# StairLights_screw.net
KiCad netlist of a schematic drawn in EAGLE
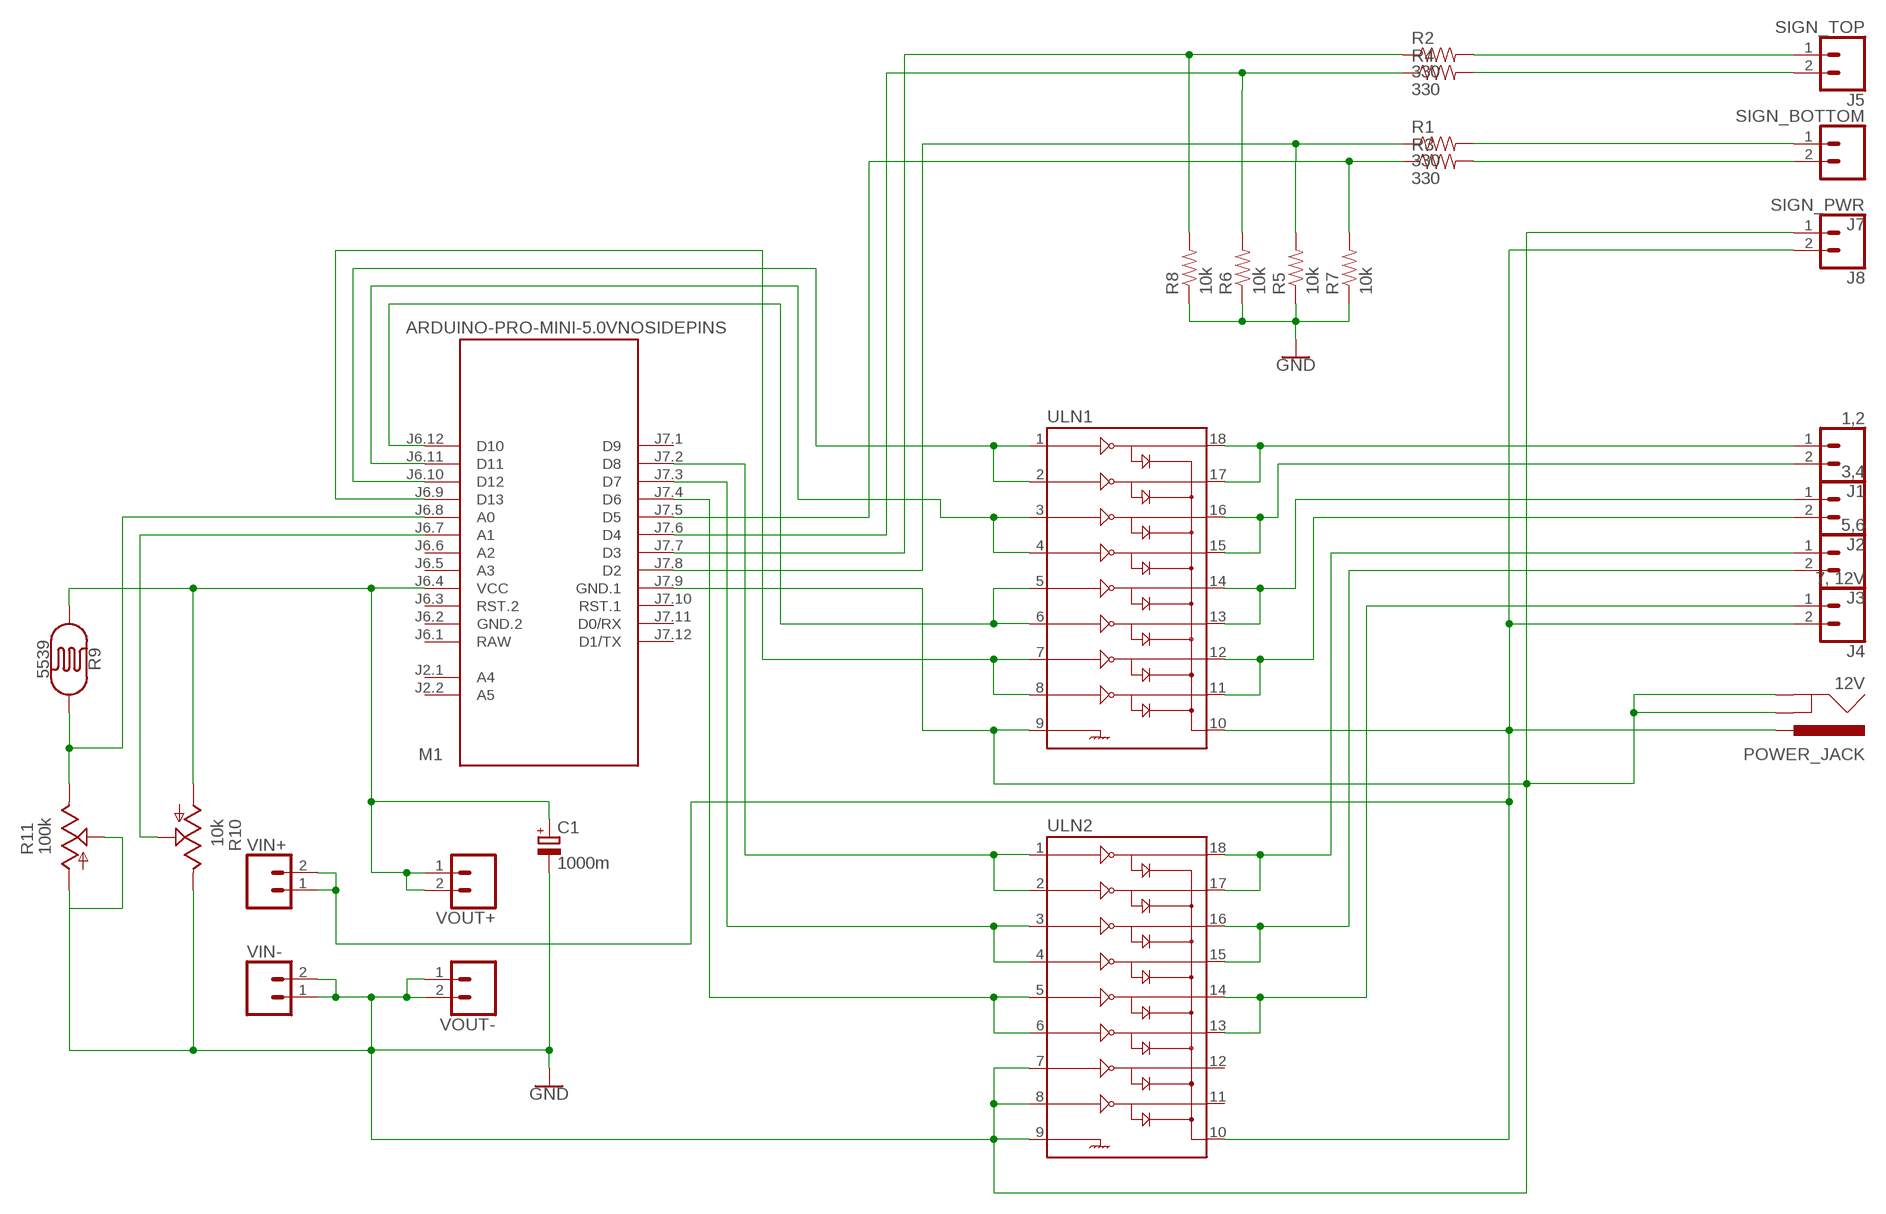
[diagram p0: schematic, sheet 1]

(export (version "E")
  (design (tool "Eeschema 10.0.6"))
  (components
    (comp (ref "12V")
      (value "POWER_JACK")
      (footprint "eagle-import:POWER_JACK_PTH")
      (libsource (lib "eagle-import") (part "POWER_JACK"))
    )
    (comp (ref "C1")
      (value "1000m")
      (footprint "eagle-import:E5-5")
      (libsource (lib "eagle-import") (part "CPOL-EUE5-5"))
    )
    (comp (ref "J1")
      (value "1,2")
      (footprint "eagle-import:SCREWTERMINAL-5MM-2")
      (libsource (lib "eagle-import") (part "CONN_025MM"))
    )
    (comp (ref "J2")
      (value "3,4")
      (footprint "eagle-import:SCREWTERMINAL-5MM-2")
      (libsource (lib "eagle-import") (part "CONN_025MM"))
    )
    (comp (ref "J3")
      (value "5,6")
      (footprint "eagle-import:SCREWTERMINAL-5MM-2")
      (libsource (lib "eagle-import") (part "CONN_025MM"))
    )
    (comp (ref "J4")
      (value "7, 12V")
      (footprint "eagle-import:SCREWTERMINAL-5MM-2")
      (libsource (lib "eagle-import") (part "CONN_025MM"))
    )
    (comp (ref "J5")
      (value "SIGN_TOP")
      (footprint "eagle-import:SCREWTERMINAL-5MM-2")
      (libsource (lib "eagle-import") (part "CONN_025MM"))
    )
    (comp (ref "J7")
      (value "SIGN_BOTTOM")
      (footprint "eagle-import:SCREWTERMINAL-5MM-2")
      (libsource (lib "eagle-import") (part "CONN_025MM"))
    )
    (comp (ref "J8")
      (value "SIGN_PWR")
      (footprint "eagle-import:SCREWTERMINAL-5MM-2")
      (libsource (lib "eagle-import") (part "CONN_025MM"))
    )
    (comp (ref "M1")
      (value "ARDUINO-PRO-MINI-5.0VNOSIDEPINS")
      (footprint "eagle-import:ARDUINO-PRO-MINI")
      (libsource (lib "eagle-import") (part "ARDUINO-PRO-MINI-NOSIDEPINS5.0V"))
    )
    (comp (ref "R1")
      (value "330")
      (footprint "eagle-import:AXIAL-0.3")
      (libsource (lib "eagle-import") (part "330OHM-HORIZ-1/10W-5%"))
    )
    (comp (ref "R2")
      (value "330")
      (footprint "eagle-import:AXIAL-0.3")
      (libsource (lib "eagle-import") (part "330OHM-HORIZ-1/10W-5%"))
    )
    (comp (ref "R3")
      (value "330")
      (footprint "eagle-import:AXIAL-0.3")
      (libsource (lib "eagle-import") (part "330OHM-HORIZ-1/10W-5%"))
    )
    (comp (ref "R4")
      (value "330")
      (footprint "eagle-import:AXIAL-0.3")
      (libsource (lib "eagle-import") (part "330OHM-HORIZ-1/10W-5%"))
    )
    (comp (ref "R5")
      (value "10k")
      (footprint "eagle-import:AXIAL-0.3")
      (libsource (lib "eagle-import") (part "330OHM-HORIZ-1/10W-5%"))
    )
    (comp (ref "R6")
      (value "10k")
      (footprint "eagle-import:AXIAL-0.3")
      (libsource (lib "eagle-import") (part "330OHM-HORIZ-1/10W-5%"))
    )
    (comp (ref "R7")
      (value "10k")
      (footprint "eagle-import:AXIAL-0.3")
      (libsource (lib "eagle-import") (part "330OHM-HORIZ-1/10W-5%"))
    )
    (comp (ref "R8")
      (value "10k")
      (footprint "eagle-import:AXIAL-0.3")
      (libsource (lib "eagle-import") (part "330OHM-HORIZ-1/10W-5%"))
    )
    (comp (ref "R9")
      (value "5539")
      (footprint "eagle-import:PHOTOCELL")
      (libsource (lib "eagle-import") (part "PHOTOCELLPTH"))
    )
    (comp (ref "R10")
      (value "10k")
      (footprint "eagle-import:S64W")
      (libsource (lib "eagle-import") (part "TRIM_US-S64W"))
    )
    (comp (ref "R11")
      (value "100k")
      (footprint "eagle-import:S64W")
      (libsource (lib "eagle-import") (part "TRIM_US-S64W"))
    )
    (comp (ref "ULN1")
      (value "ULN2803DIP")
      (footprint "eagle-import:DIL18")
      (libsource (lib "eagle-import") (part "ULN2803DIP"))
    )
    (comp (ref "ULN2")
      (value "ULN2803DIP")
      (footprint "eagle-import:DIL18")
      (libsource (lib "eagle-import") (part "ULN2803DIP"))
    )
    (comp (ref "VIN+")
      (value "CONN_02")
      (footprint "eagle-import:1X02")
      (libsource (lib "eagle-import") (part "SparkFun-Connectors_513_CONN_02"))
    )
    (comp (ref "VIN-")
      (value "CONN_02")
      (footprint "eagle-import:1X02")
      (libsource (lib "eagle-import") (part "SparkFun-Connectors_513_CONN_02"))
    )
    (comp (ref "VOUT+")
      (value "CONN_02")
      (footprint "eagle-import:1X02")
      (libsource (lib "eagle-import") (part "SparkFun-Connectors_513_CONN_02"))
    )
    (comp (ref "VOUT-")
      (value "CONN_02")
      (footprint "eagle-import:1X02")
      (libsource (lib "eagle-import") (part "SparkFun-Connectors_513_CONN_02"))
    )
  )
  (nets
    (net (code "1") (name "/GND.2") (class "Default")
      (node (ref "M1") (pin "J6.2") (pinfunction "GND.2_J6.2") (pintype "power_in"))
    )
    (net (code "2") (name "/RAW") (class "Default")
      (node (ref "M1") (pin "J6.1") (pinfunction "RAW_J6.1") (pintype "power_in"))
    )
    (net (code "3") (name "GND") (class "Default")
      (node (ref "12V") (pin "GND") (pinfunction "GND_GND") (pintype "bidirectional"))
      (node (ref "12V") (pin "GNDBREAK") (pinfunction "GNDBREAK_GNDBREAK") (pintype "bidirectional"))
      (node (ref "C1") (pin "-") (pinfunction "-_-") (pintype "passive"))
      (node (ref "J8") (pin "1") (pinfunction "1_1") (pintype "passive"))
      (node (ref "M1") (pin "J7.9") (pinfunction "GND.1_J7.9") (pintype "power_in"))
      (node (ref "R10") (pin "E") (pinfunction "E_E") (pintype "passive"))
      (node (ref "R11") (pin "A") (pinfunction "A_A") (pintype "passive"))
      (node (ref "R11") (pin "S") (pinfunction "S_S") (pintype "passive"))
      (node (ref "R5") (pin "P$1") (pinfunction "1_P$1") (pintype "passive"))
      (node (ref "R6") (pin "P$1") (pinfunction "1_P$1") (pintype "passive"))
      (node (ref "R7") (pin "P$1") (pinfunction "1_P$1") (pintype "passive"))
      (node (ref "R8") (pin "P$1") (pinfunction "1_P$1") (pintype "passive"))
      (node (ref "ULN1") (pin "9") (pinfunction "9_9") (pintype "bidirectional"))
      (node (ref "ULN2") (pin "7") (pinfunction "7_7") (pintype "bidirectional"))
      (node (ref "ULN2") (pin "8") (pinfunction "8_8") (pintype "bidirectional"))
      (node (ref "ULN2") (pin "9") (pinfunction "9_9") (pintype "bidirectional"))
      (node (ref "VIN-") (pin "1") (pinfunction "1_1") (pintype "passive"))
      (node (ref "VIN-") (pin "2") (pinfunction "2_2") (pintype "passive"))
      (node (ref "VOUT-") (pin "1") (pinfunction "1_1") (pintype "passive"))
      (node (ref "VOUT-") (pin "2") (pinfunction "2_2") (pintype "passive"))
    )
    (net (code "4") (name "Net-(12V-PadPWR)") (class "Default")
      (node (ref "12V") (pin "PWR") (pinfunction "PWR_PWR") (pintype "bidirectional"))
      (node (ref "J4") (pin "2") (pinfunction "2_2") (pintype "passive"))
      (node (ref "J8") (pin "2") (pinfunction "2_2") (pintype "passive"))
      (node (ref "ULN1") (pin "10") (pinfunction "10_10") (pintype "bidirectional"))
      (node (ref "ULN2") (pin "10") (pinfunction "10_10") (pintype "bidirectional"))
      (node (ref "VIN+") (pin "1") (pinfunction "1_1") (pintype "passive"))
      (node (ref "VIN+") (pin "2") (pinfunction "2_2") (pintype "passive"))
    )
    (net (code "5") (name "Net-(J1-Pad1)") (class "Default")
      (node (ref "J1") (pin "1") (pinfunction "1_1") (pintype "passive"))
      (node (ref "ULN1") (pin "17") (pinfunction "17_17") (pintype "bidirectional"))
      (node (ref "ULN1") (pin "18") (pinfunction "18_18") (pintype "bidirectional"))
    )
    (net (code "6") (name "Net-(J1-Pad2)") (class "Default")
      (node (ref "J1") (pin "2") (pinfunction "2_2") (pintype "passive"))
      (node (ref "ULN1") (pin "15") (pinfunction "15_15") (pintype "bidirectional"))
      (node (ref "ULN1") (pin "16") (pinfunction "16_16") (pintype "bidirectional"))
    )
    (net (code "7") (name "Net-(J2-Pad1)") (class "Default")
      (node (ref "J2") (pin "1") (pinfunction "1_1") (pintype "passive"))
      (node (ref "ULN1") (pin "13") (pinfunction "13_13") (pintype "bidirectional"))
      (node (ref "ULN1") (pin "14") (pinfunction "14_14") (pintype "bidirectional"))
    )
    (net (code "8") (name "Net-(J2-Pad2)") (class "Default")
      (node (ref "J2") (pin "2") (pinfunction "2_2") (pintype "passive"))
      (node (ref "ULN1") (pin "11") (pinfunction "11_11") (pintype "bidirectional"))
      (node (ref "ULN1") (pin "12") (pinfunction "12_12") (pintype "bidirectional"))
    )
    (net (code "9") (name "Net-(J3-Pad1)") (class "Default")
      (node (ref "J3") (pin "1") (pinfunction "1_1") (pintype "passive"))
      (node (ref "ULN2") (pin "17") (pinfunction "17_17") (pintype "bidirectional"))
      (node (ref "ULN2") (pin "18") (pinfunction "18_18") (pintype "bidirectional"))
    )
    (net (code "10") (name "Net-(J3-Pad2)") (class "Default")
      (node (ref "J3") (pin "2") (pinfunction "2_2") (pintype "passive"))
      (node (ref "ULN2") (pin "15") (pinfunction "15_15") (pintype "bidirectional"))
      (node (ref "ULN2") (pin "16") (pinfunction "16_16") (pintype "bidirectional"))
    )
    (net (code "11") (name "Net-(J4-Pad1)") (class "Default")
      (node (ref "J4") (pin "1") (pinfunction "1_1") (pintype "passive"))
      (node (ref "ULN2") (pin "13") (pinfunction "13_13") (pintype "bidirectional"))
      (node (ref "ULN2") (pin "14") (pinfunction "14_14") (pintype "bidirectional"))
    )
    (net (code "12") (name "Net-(M1-A0)") (class "Default")
      (node (ref "M1") (pin "J6.8") (pinfunction "A0_J6.8") (pintype "bidirectional"))
      (node (ref "R11") (pin "E") (pinfunction "E_E") (pintype "passive"))
      (node (ref "R9") (pin "2") (pinfunction "P$2_2") (pintype "bidirectional"))
    )
    (net (code "13") (name "Net-(M1-A1)") (class "Default")
      (node (ref "M1") (pin "J6.7") (pinfunction "A1_J6.7") (pintype "bidirectional"))
      (node (ref "R10") (pin "S") (pinfunction "S_S") (pintype "passive"))
    )
    (net (code "14") (name "Net-(M1-D2)") (class "Default")
      (node (ref "M1") (pin "J7.8") (pinfunction "D2_J7.8") (pintype "bidirectional"))
      (node (ref "R1") (pin "P$1") (pinfunction "1_P$1") (pintype "passive"))
      (node (ref "R5") (pin "P$2") (pinfunction "2_P$2") (pintype "passive"))
    )
    (net (code "15") (name "Net-(M1-D3)") (class "Default")
      (node (ref "M1") (pin "J7.7") (pinfunction "D3_J7.7") (pintype "bidirectional"))
      (node (ref "R2") (pin "P$1") (pinfunction "1_P$1") (pintype "passive"))
      (node (ref "R8") (pin "P$2") (pinfunction "2_P$2") (pintype "passive"))
    )
    (net (code "16") (name "Net-(M1-D4)") (class "Default")
      (node (ref "M1") (pin "J7.6") (pinfunction "D4_J7.6") (pintype "bidirectional"))
      (node (ref "R4") (pin "P$1") (pinfunction "1_P$1") (pintype "passive"))
      (node (ref "R6") (pin "P$2") (pinfunction "2_P$2") (pintype "passive"))
    )
    (net (code "17") (name "Net-(M1-D5)") (class "Default")
      (node (ref "M1") (pin "J7.5") (pinfunction "D5_J7.5") (pintype "bidirectional"))
      (node (ref "R3") (pin "P$1") (pinfunction "1_P$1") (pintype "passive"))
      (node (ref "R7") (pin "P$2") (pinfunction "2_P$2") (pintype "passive"))
    )
    (net (code "18") (name "Net-(M1-D6)") (class "Default")
      (node (ref "M1") (pin "J7.4") (pinfunction "D6_J7.4") (pintype "bidirectional"))
      (node (ref "ULN2") (pin "5") (pinfunction "5_5") (pintype "bidirectional"))
      (node (ref "ULN2") (pin "6") (pinfunction "6_6") (pintype "bidirectional"))
    )
    (net (code "19") (name "Net-(M1-D7)") (class "Default")
      (node (ref "M1") (pin "J7.3") (pinfunction "D7_J7.3") (pintype "bidirectional"))
      (node (ref "ULN2") (pin "3") (pinfunction "3_3") (pintype "bidirectional"))
      (node (ref "ULN2") (pin "4") (pinfunction "4_4") (pintype "bidirectional"))
    )
    (net (code "20") (name "Net-(M1-D8)") (class "Default")
      (node (ref "M1") (pin "J7.2") (pinfunction "D8_J7.2") (pintype "bidirectional"))
      (node (ref "ULN2") (pin "1") (pinfunction "1_1") (pintype "bidirectional"))
      (node (ref "ULN2") (pin "2") (pinfunction "2_2") (pintype "bidirectional"))
    )
    (net (code "21") (name "Net-(M1-D10)") (class "Default")
      (node (ref "M1") (pin "J6.12") (pinfunction "D10_J6.12") (pintype "bidirectional"))
      (node (ref "ULN1") (pin "5") (pinfunction "5_5") (pintype "bidirectional"))
      (node (ref "ULN1") (pin "6") (pinfunction "6_6") (pintype "bidirectional"))
    )
    (net (code "22") (name "Net-(M1-D11)") (class "Default")
      (node (ref "M1") (pin "J6.11") (pinfunction "D11_J6.11") (pintype "bidirectional"))
      (node (ref "ULN1") (pin "3") (pinfunction "3_3") (pintype "bidirectional"))
      (node (ref "ULN1") (pin "4") (pinfunction "4_4") (pintype "bidirectional"))
    )
    (net (code "23") (name "Net-(M1-D12)") (class "Default")
      (node (ref "M1") (pin "J6.10") (pinfunction "D12_J6.10") (pintype "bidirectional"))
      (node (ref "ULN1") (pin "1") (pinfunction "1_1") (pintype "bidirectional"))
      (node (ref "ULN1") (pin "2") (pinfunction "2_2") (pintype "bidirectional"))
    )
    (net (code "24") (name "Net-(M1-D13)") (class "Default")
      (node (ref "M1") (pin "J6.9") (pinfunction "D13_J6.9") (pintype "bidirectional"))
      (node (ref "ULN1") (pin "7") (pinfunction "7_7") (pintype "bidirectional"))
      (node (ref "ULN1") (pin "8") (pinfunction "8_8") (pintype "bidirectional"))
    )
    (net (code "25") (name "Net-(M1-VCC)") (class "Default")
      (node (ref "C1") (pin "+") (pinfunction "+_+") (pintype "passive"))
      (node (ref "M1") (pin "J6.4") (pinfunction "VCC_J6.4") (pintype "power_in"))
      (node (ref "R10") (pin "A") (pinfunction "A_A") (pintype "passive"))
      (node (ref "R9") (pin "1") (pinfunction "P$1_1") (pintype "bidirectional"))
      (node (ref "VOUT+") (pin "1") (pinfunction "1_1") (pintype "passive"))
      (node (ref "VOUT+") (pin "2") (pinfunction "2_2") (pintype "passive"))
    )
    (net (code "26") (name "Net-(R1-2)") (class "Default")
      (node (ref "J7") (pin "1") (pinfunction "1_1") (pintype "passive"))
      (node (ref "R1") (pin "P$2") (pinfunction "2_P$2") (pintype "passive"))
    )
    (net (code "27") (name "Net-(R2-2)") (class "Default")
      (node (ref "J5") (pin "1") (pinfunction "1_1") (pintype "passive"))
      (node (ref "R2") (pin "P$2") (pinfunction "2_P$2") (pintype "passive"))
    )
    (net (code "28") (name "Net-(R3-2)") (class "Default")
      (node (ref "J7") (pin "2") (pinfunction "2_2") (pintype "passive"))
      (node (ref "R3") (pin "P$2") (pinfunction "2_P$2") (pintype "passive"))
    )
    (net (code "29") (name "Net-(R4-2)") (class "Default")
      (node (ref "J5") (pin "2") (pinfunction "2_2") (pintype "passive"))
      (node (ref "R4") (pin "P$2") (pinfunction "2_P$2") (pintype "passive"))
    )
    (net (code "30") (name "unconnected-(M1-A2-PadJ6.6)") (class "Default")
      (node (ref "M1") (pin "J6.6") (pinfunction "A2_J6.6") (pintype "bidirectional"))
    )
    (net (code "31") (name "unconnected-(M1-A3-PadJ6.5)") (class "Default")
      (node (ref "M1") (pin "J6.5") (pinfunction "A3_J6.5") (pintype "bidirectional"))
    )
    (net (code "32") (name "unconnected-(M1-A4-PadJ2.1)") (class "Default")
      (node (ref "M1") (pin "J2.1") (pinfunction "A4_J2.1") (pintype "bidirectional"))
    )
    (net (code "33") (name "unconnected-(M1-A5-PadJ2.2)") (class "Default")
      (node (ref "M1") (pin "J2.2") (pinfunction "A5_J2.2") (pintype "bidirectional"))
    )
    (net (code "34") (name "unconnected-(M1-D0{slash}RX-PadJ7.11)") (class "Default")
      (node (ref "M1") (pin "J7.11") (pinfunction "D0/RX_J7.11") (pintype "bidirectional"))
    )
    (net (code "35") (name "unconnected-(M1-D1{slash}TX-PadJ7.12)") (class "Default")
      (node (ref "M1") (pin "J7.12") (pinfunction "D1/TX_J7.12") (pintype "bidirectional"))
    )
    (net (code "36") (name "unconnected-(M1-D9-PadJ7.1)") (class "Default")
      (node (ref "M1") (pin "J7.1") (pinfunction "D9_J7.1") (pintype "bidirectional"))
    )
    (net (code "37") (name "unconnected-(M1-RST.1-PadJ7.10)") (class "Default")
      (node (ref "M1") (pin "J7.10") (pinfunction "RST.1_J7.10") (pintype "bidirectional"))
    )
    (net (code "38") (name "unconnected-(M1-RST.2-PadJ6.3)") (class "Default")
      (node (ref "M1") (pin "J6.3") (pinfunction "RST.2_J6.3") (pintype "bidirectional"))
    )
    (net (code "39") (name "unconnected-(ULN2-Pad11)") (class "Default")
      (node (ref "ULN2") (pin "11") (pinfunction "11_11") (pintype "bidirectional"))
    )
    (net (code "40") (name "unconnected-(ULN2-Pad12)") (class "Default")
      (node (ref "ULN2") (pin "12") (pinfunction "12_12") (pintype "bidirectional"))
    )
  )
)
